# LTE_GPS_Power.net
KiCad netlist of a schematic drawn in Altium Designer
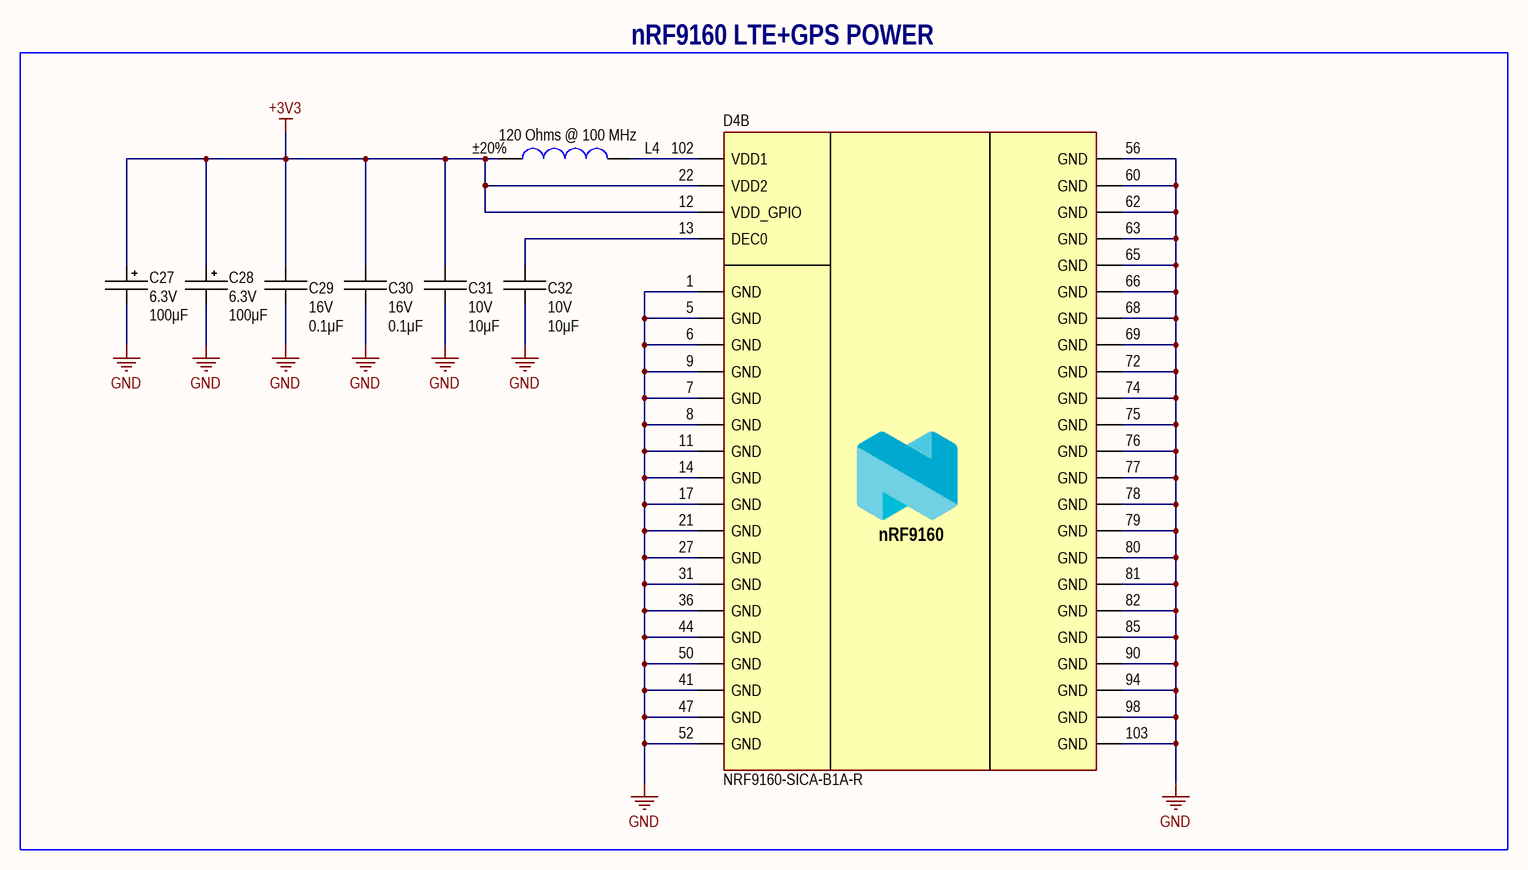
[diagram p0: LTE+GPS_Power.SchDoc]

(export (version "E")
  (design (tool "Eeschema 10.0.6"))
  (components
    (comp (ref "C27")
      (value "100μF")
      (footprint "CAP: TANTAL-A")
      (description "100 µF Molded Tantalum Polymer Capacitor 6.3 V 1206 (3216 Metric) 100mOhm @ 100kHz")
      (fields
        (field (name "MANUFACTURER") "AVX")
        (field (name "PARTNUMBER") "TCJA107M006R0100")
        (field (name "VOLTAGE") "6.3V")
      )
      (libsource (lib "capacitor") (part "Tantal_A"))
    )
    (comp (ref "C28")
      (value "100μF")
      (footprint "CAP: TANTAL-A")
      (description "100 µF Molded Tantalum Polymer Capacitor 6.3 V 1206 (3216 Metric) 100mOhm @ 100kHz")
      (fields
        (field (name "MANUFACTURER") "AVX")
        (field (name "PARTNUMBER") "TCJA107M006R0100")
        (field (name "VOLTAGE") "6.3V")
      )
      (libsource (lib "capacitor") (part "Tantal_A"))
    )
    (comp (ref "C29")
      (value "0.1μF")
      (footprint "CAP: 0805")
      (fields
        (field (name "MANUFACTURER") "Yageo")
        (field (name "PARTNUMBER") "CC0805KRX7R7BB104")
        (field (name "VALUEMANUFACTURERPARTNUMBER") "Ceramic capacitor, 0.1μF, X7R, ±10%, 16V, 0805, -55...+125°C")
        (field (name "VOLTAGE") "16V")
      )
      (libsource (lib "capacitor") (part "Ceramic_0805"))
    )
    (comp (ref "C30")
      (value "0.1μF")
      (footprint "CAP: 0805")
      (fields
        (field (name "MANUFACTURER") "Yageo")
        (field (name "PARTNUMBER") "CC0805KRX7R7BB104")
        (field (name "VALUEMANUFACTURERPARTNUMBER") "Ceramic capacitor, 0.1μF, X7R, ±10%, 16V, 0805, -55...+125°C")
        (field (name "VOLTAGE") "16V")
      )
      (libsource (lib "capacitor") (part "Ceramic_0805"))
    )
    (comp (ref "C31")
      (value "10μF")
      (footprint "CAP: 0805")
      (description "10 µF ±10% 10V Ceramic Capacitor X7R 0805 (2012 Metric)")
      (fields
        (field (name "MANUFACTURER") "Yageo")
        (field (name "PARTNUMBER") "CC0805KFX7R6BB106")
        (field (name "VOLTAGE") "10V")
      )
      (libsource (lib "capacitor") (part "Ceramic_0805"))
    )
    (comp (ref "C32")
      (value "10μF")
      (footprint "CAP: 0805")
      (description "10 µF ±10% 10V Ceramic Capacitor X7R 0805 (2012 Metric)")
      (fields
        (field (name "MANUFACTURER") "Yageo")
        (field (name "PARTNUMBER") "CC0805KFX7R6BB106")
        (field (name "VOLTAGE") "10V")
      )
      (libsource (lib "capacitor") (part "Ceramic_0805"))
    )
    (comp (ref "D4")
      (value "~")
      (footprint "MOD: NRF9160")
      (description "LTE/GSM module")
      (fields
        (field (name "MANUFACTURER") "Nordic Semiconductor")
        (field (name "VALUEMANUFACTURERPARTNUMBER") "LTE/GSM module, LTE-M/NB-IoT/GPS, 2.4GHz, , , , , 3...5.5V, -40...+85°C, 127-LGA")
        (field (name "PARTNUMBER") "NRF9160-SICA-B1A-R")
      )
      (libsource (lib "MyLib") (part "nRF9160"))
    )
    (comp (ref "L4")
      (value "120 Ohms @ 100 MHz")
      (footprint "IND: 0805")
      (description "120 Ohms @ 100 MHz 1 Power Line Ferrite Bead 0805 (2012 Metric) 3A 30mOhm")
      (fields
        (field (name "MANUFACTURER") "Murata Electronics")
        (field (name "PARTNUMBER") "BLM21PG121SH1D")
        (field (name "TOLERANCE") "±20%")
      )
      (libsource (lib "inductor") (part "Inductor_0805"))
    )
  )
  (nets
    (net (code "1") (name "+3V3") (class "Default")
      (node (ref "C27") (pin "1") (pinfunction "1_1") (pintype "passive"))
      (node (ref "C28") (pin "1") (pinfunction "1_1") (pintype "passive"))
      (node (ref "C29") (pin "2") (pinfunction "2_2") (pintype "passive"))
      (node (ref "C30") (pin "2") (pinfunction "2_2") (pintype "passive"))
      (node (ref "C31") (pin "2") (pinfunction "2_2") (pintype "passive"))
      (node (ref "D4") (pin "12") (pinfunction "VDD_GPIO_12") (pintype "power_in"))
      (node (ref "D4") (pin "22") (pinfunction "VDD2_22") (pintype "power_in"))
      (node (ref "L4") (pin "2") (pinfunction "2_2") (pintype "passive"))
    )
    (net (code "2") (name "GND") (class "Default")
      (node (ref "C27") (pin "2") (pinfunction "2_2") (pintype "passive"))
      (node (ref "C28") (pin "2") (pinfunction "2_2") (pintype "passive"))
      (node (ref "C29") (pin "1") (pinfunction "1_1") (pintype "passive"))
      (node (ref "C30") (pin "1") (pinfunction "1_1") (pintype "passive"))
      (node (ref "C31") (pin "1") (pinfunction "1_1") (pintype "passive"))
      (node (ref "C32") (pin "1") (pinfunction "1_1") (pintype "passive"))
      (node (ref "D4") (pin "1") (pinfunction "GND_1") (pintype "power_in"))
      (node (ref "D4") (pin "103") (pinfunction "GND_103") (pintype "power_in"))
      (node (ref "D4") (pin "11") (pinfunction "GND_11") (pintype "passive"))
      (node (ref "D4") (pin "14") (pinfunction "GND_14") (pintype "power_in"))
      (node (ref "D4") (pin "17") (pinfunction "GND_17") (pintype "power_in"))
      (node (ref "D4") (pin "21") (pinfunction "GND_21") (pintype "power_in"))
      (node (ref "D4") (pin "27") (pinfunction "GND_27") (pintype "power_in"))
      (node (ref "D4") (pin "31") (pinfunction "GND_31") (pintype "power_in"))
      (node (ref "D4") (pin "36") (pinfunction "GND_36") (pintype "power_in"))
      (node (ref "D4") (pin "41") (pinfunction "GND_41") (pintype "power_in"))
      (node (ref "D4") (pin "44") (pinfunction "GND_44") (pintype "power_in"))
      (node (ref "D4") (pin "47") (pinfunction "GND_47") (pintype "power_in"))
      (node (ref "D4") (pin "5") (pinfunction "GND_5") (pintype "power_in"))
      (node (ref "D4") (pin "50") (pinfunction "GND_50") (pintype "power_in"))
      (node (ref "D4") (pin "52") (pinfunction "GND_52") (pintype "power_in"))
      (node (ref "D4") (pin "56") (pinfunction "GND_56") (pintype "power_in"))
      (node (ref "D4") (pin "6") (pinfunction "GND_6") (pintype "passive"))
      (node (ref "D4") (pin "60") (pinfunction "GND_60") (pintype "power_in"))
      (node (ref "D4") (pin "62") (pinfunction "GND_62") (pintype "power_in"))
      (node (ref "D4") (pin "63") (pinfunction "GND_63") (pintype "power_in"))
      (node (ref "D4") (pin "65") (pinfunction "GND_65") (pintype "power_in"))
      (node (ref "D4") (pin "66") (pinfunction "GND_66") (pintype "power_in"))
      (node (ref "D4") (pin "68") (pinfunction "GND_68") (pintype "passive"))
      (node (ref "D4") (pin "69") (pinfunction "GND_69") (pintype "passive"))
      (node (ref "D4") (pin "7") (pinfunction "GND_7") (pintype "passive"))
      (node (ref "D4") (pin "72") (pinfunction "GND_72") (pintype "power_in"))
      (node (ref "D4") (pin "74") (pinfunction "GND_74") (pintype "power_in"))
      (node (ref "D4") (pin "75") (pinfunction "GND_75") (pintype "power_in"))
      (node (ref "D4") (pin "76") (pinfunction "GND_76") (pintype "power_in"))
      (node (ref "D4") (pin "77") (pinfunction "GND_77") (pintype "power_in"))
      (node (ref "D4") (pin "78") (pinfunction "GND_78") (pintype "power_in"))
      (node (ref "D4") (pin "79") (pinfunction "GND_79") (pintype "power_in"))
      (node (ref "D4") (pin "8") (pinfunction "GND_8") (pintype "passive"))
      (node (ref "D4") (pin "80") (pinfunction "GND_80") (pintype "power_in"))
      (node (ref "D4") (pin "81") (pinfunction "GND_81") (pintype "power_in"))
      (node (ref "D4") (pin "82") (pinfunction "GND_82") (pintype "power_in"))
      (node (ref "D4") (pin "85") (pinfunction "GND_85") (pintype "power_in"))
      (node (ref "D4") (pin "9") (pinfunction "GND_9") (pintype "power_in"))
      (node (ref "D4") (pin "90") (pinfunction "GND_90") (pintype "power_in"))
      (node (ref "D4") (pin "94") (pinfunction "GND_94") (pintype "power_in"))
      (node (ref "D4") (pin "98") (pinfunction "GND_98") (pintype "power_in"))
    )
    (net (code "3") (name "Net-(D4B-DEC0)") (class "Default")
      (node (ref "C32") (pin "2") (pinfunction "2_2") (pintype "passive"))
      (node (ref "D4") (pin "13") (pinfunction "DEC0_13") (pintype "power_in"))
    )
    (net (code "4") (name "Net-(D4B-VDD1)") (class "Default")
      (node (ref "D4") (pin "102") (pinfunction "VDD1_102") (pintype "power_in"))
      (node (ref "L4") (pin "1") (pinfunction "1_1") (pintype "passive"))
    )
  )
)
